# Shawn_sMega.net
KiCad netlist of a schematic drawn in EAGLE
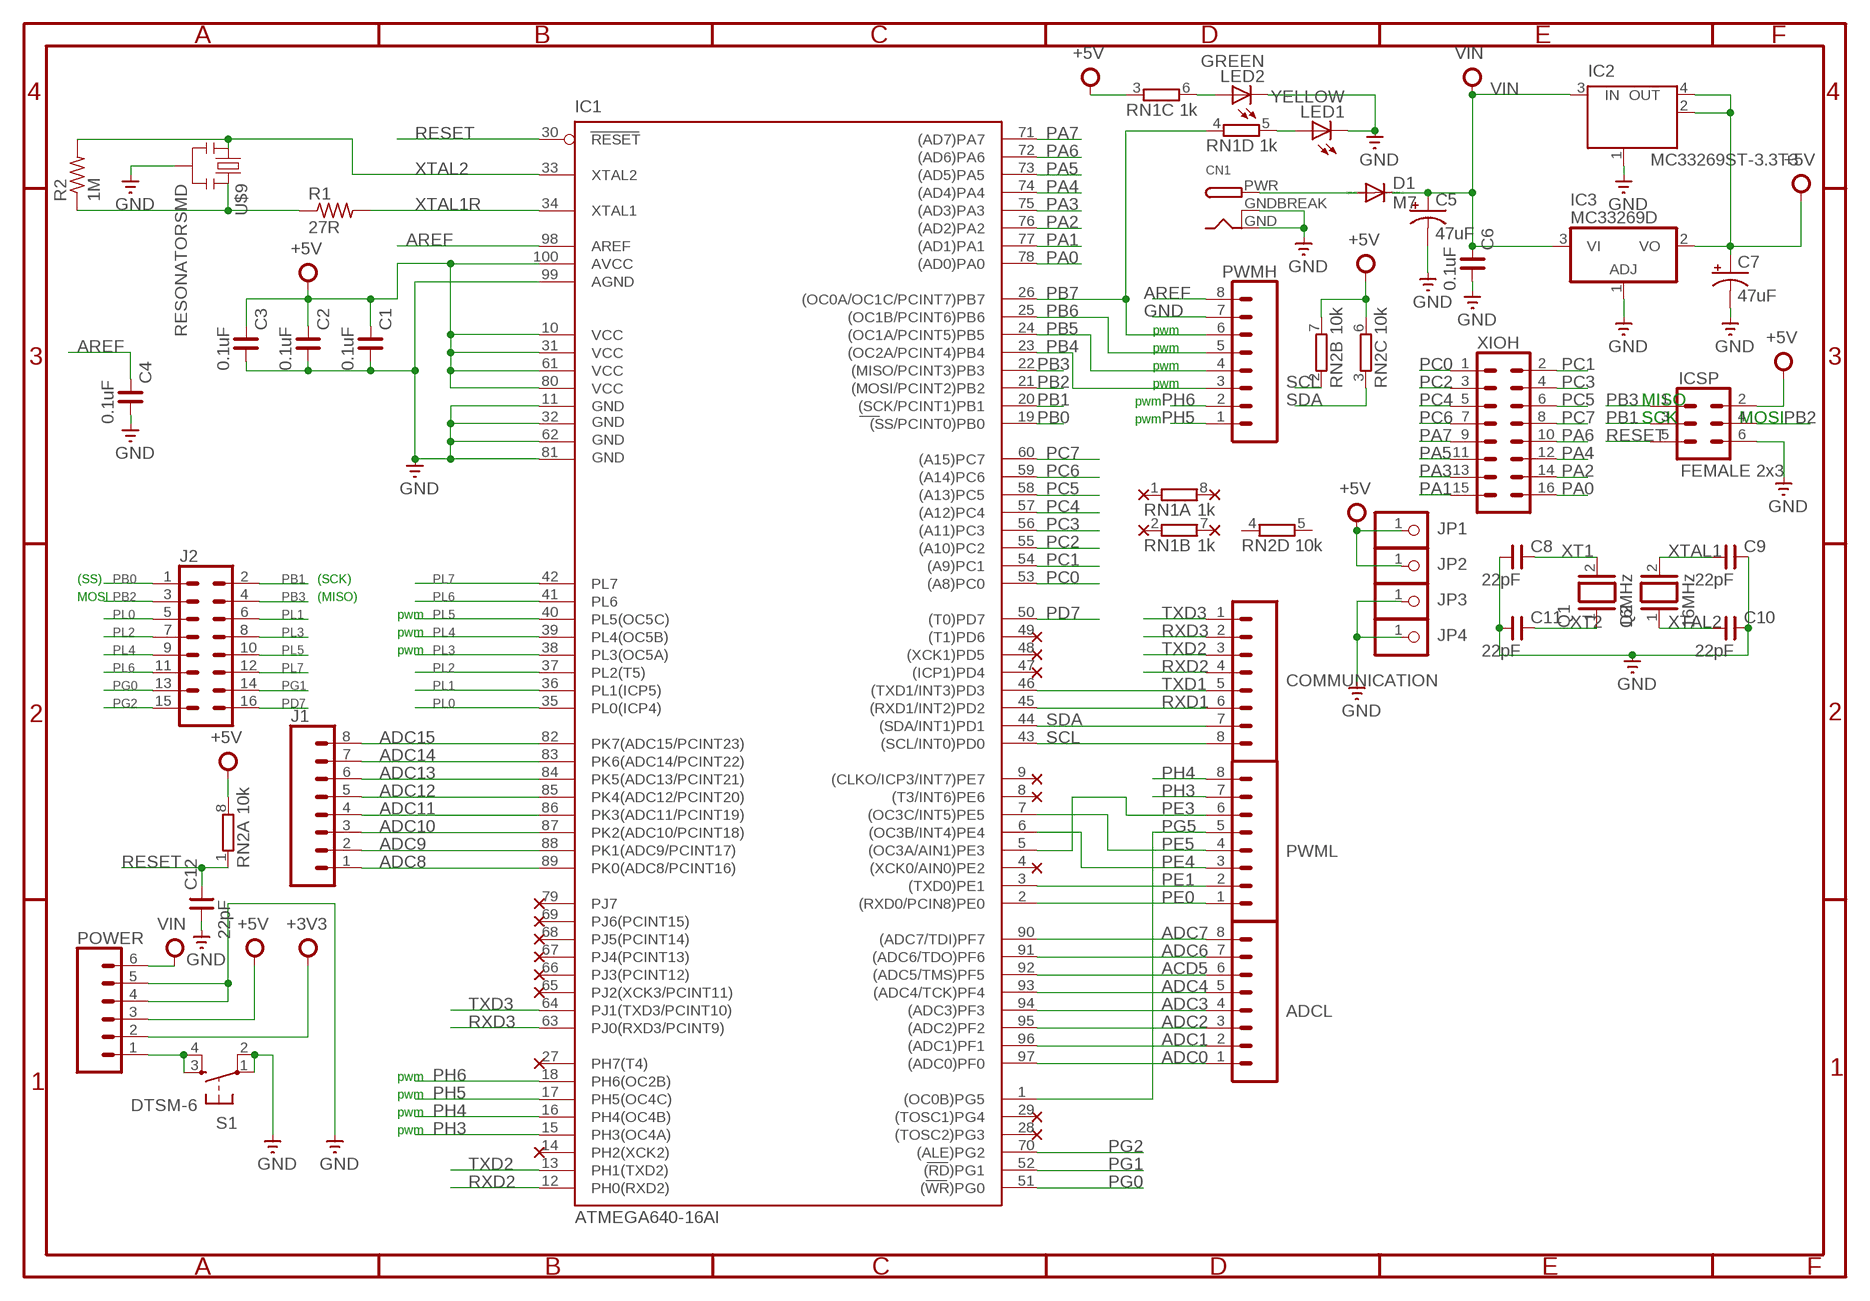
[diagram p0: schematic, sheet 1, part 1 of 2]
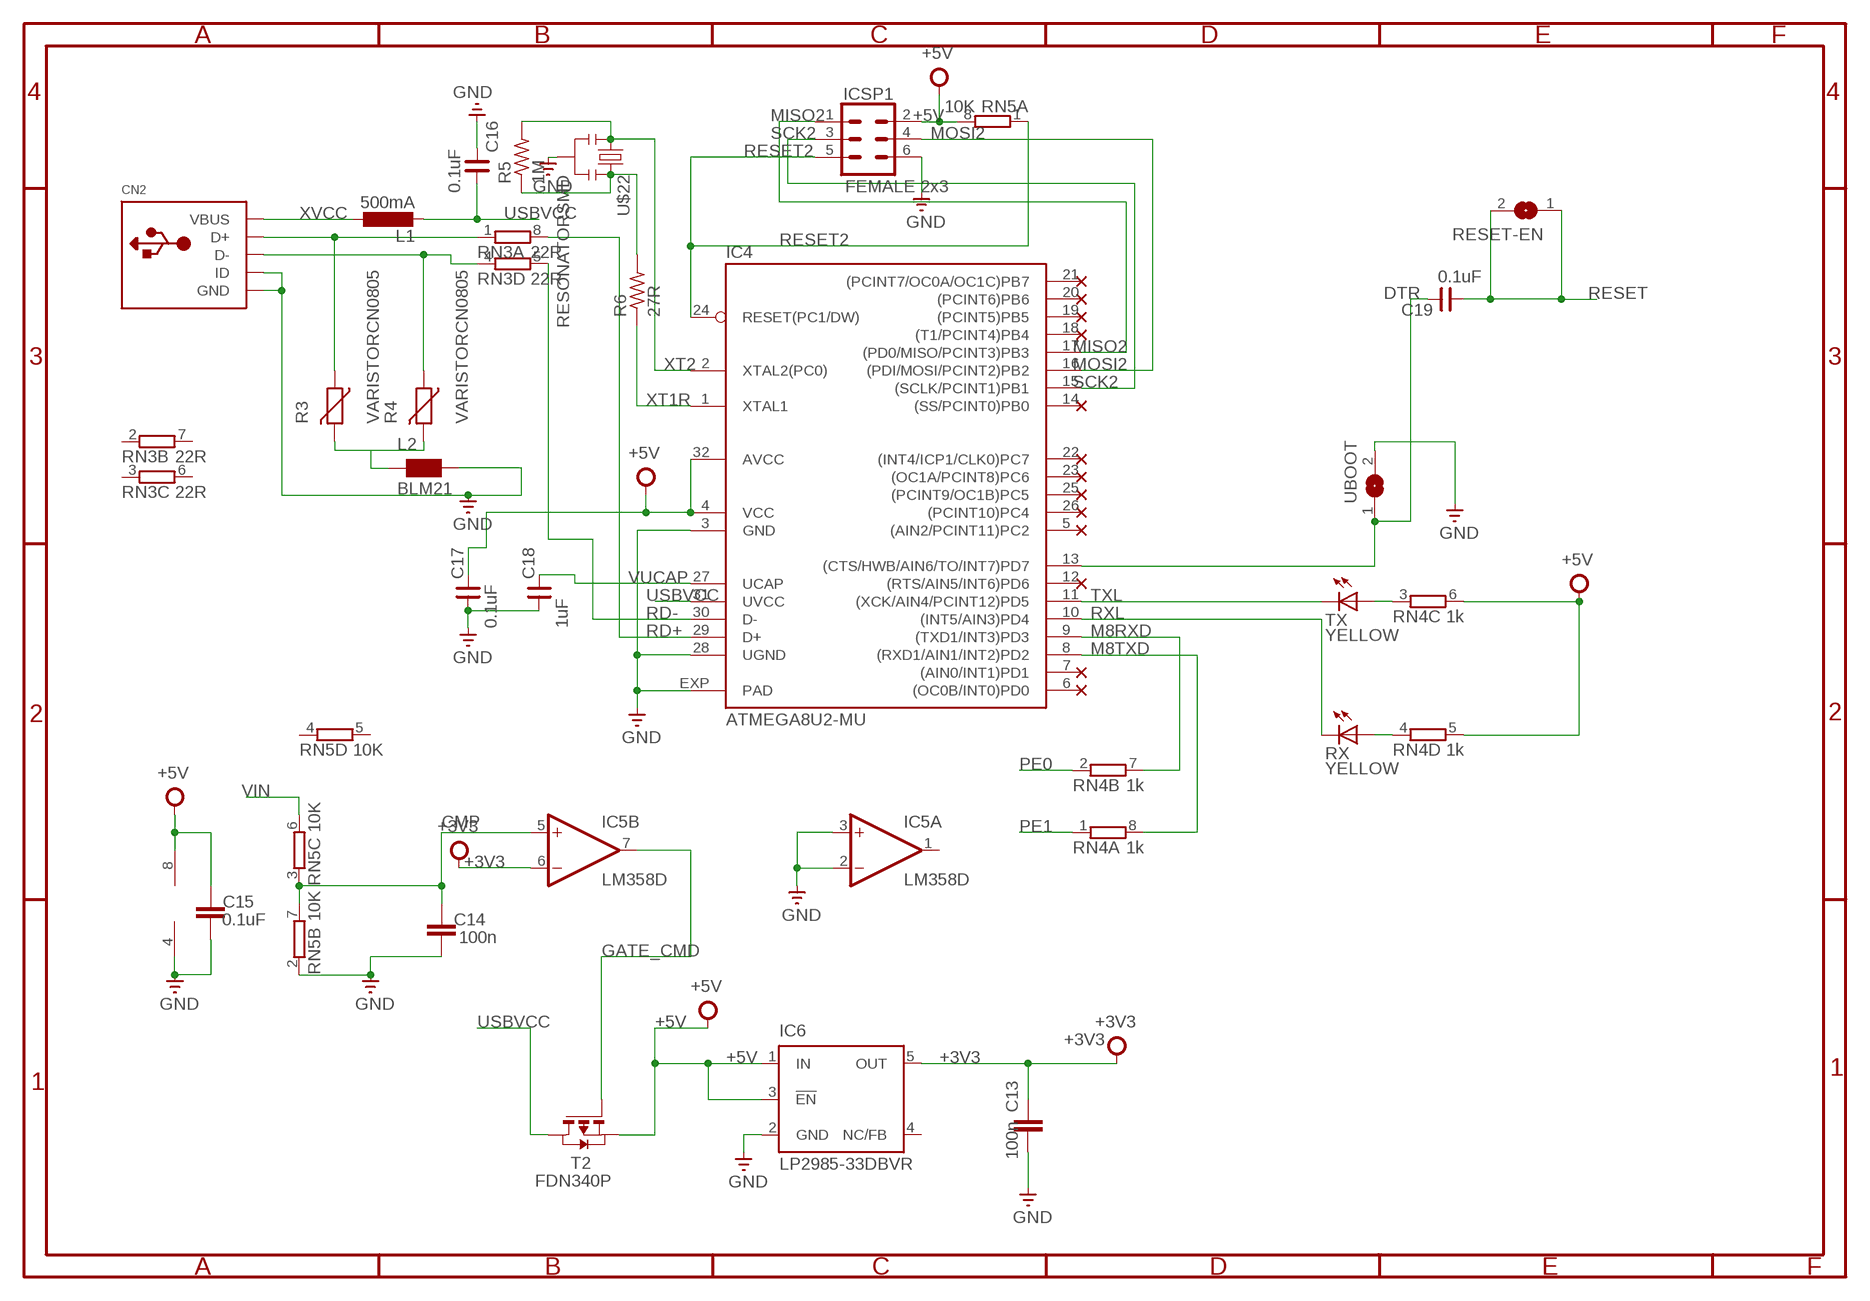
[diagram p1: schematic, sheet 1, part 2 of 2]

(export (version "E")
  (design (tool "Eeschema 10.0.6"))
  (components
    (comp (ref "ADCL")
      (value "CONN_08\"")
      (footprint "eagle-import:1X08")
      (libsource (lib "eagle-import") (part "CONN_08{dblquote}"))
    )
    (comp (ref "C1")
      (value "0.1uF")
      (footprint "eagle-import:C0805")
      (libsource (lib "eagle-import") (part "C_0805"))
    )
    (comp (ref "C2")
      (value "0.1uF")
      (footprint "eagle-import:C0805")
      (libsource (lib "eagle-import") (part "C_0805"))
    )
    (comp (ref "C3")
      (value "0.1uF")
      (footprint "eagle-import:C0805")
      (libsource (lib "eagle-import") (part "C_0805"))
    )
    (comp (ref "C4")
      (value "0.1uF")
      (footprint "eagle-import:C0805")
      (libsource (lib "eagle-import") (part "C_0805"))
    )
    (comp (ref "C5")
      (value "47uF")
      (footprint "eagle-import:PANASONIC_D")
      (libsource (lib "eagle-import") (part "CPOL-USD"))
    )
    (comp (ref "C6")
      (value "0.1uF")
      (footprint "eagle-import:C0805")
      (libsource (lib "eagle-import") (part "C_0805"))
    )
    (comp (ref "C7")
      (value "47uF")
      (footprint "eagle-import:PANASONIC_D")
      (libsource (lib "eagle-import") (part "CPOL-USD"))
    )
    (comp (ref "C8")
      (value "22pF")
      (footprint "eagle-import:0805")
      (libsource (lib "eagle-import") (part "CNP-0805"))
    )
    (comp (ref "C9")
      (value "22pF")
      (footprint "eagle-import:0805")
      (libsource (lib "eagle-import") (part "CNP-0805"))
    )
    (comp (ref "C10")
      (value "22pF")
      (footprint "eagle-import:0805")
      (libsource (lib "eagle-import") (part "CNP-0805"))
    )
    (comp (ref "C11")
      (value "22pF")
      (footprint "eagle-import:0805")
      (libsource (lib "eagle-import") (part "CNP-0805"))
    )
    (comp (ref "C12")
      (value "22pF")
      (footprint "eagle-import:0805")
      (libsource (lib "eagle-import") (part "CNP-0805"))
    )
    (comp (ref "C13")
      (value "100n")
      (footprint "eagle-import:C0603-ROUND")
      (libsource (lib "eagle-import") (part "C-EU0603-RND"))
    )
    (comp (ref "C14")
      (value "100n")
      (footprint "eagle-import:C0603-ROUND")
      (libsource (lib "eagle-import") (part "C-EU0603-RND"))
    )
    (comp (ref "C15")
      (value "0.1uF")
      (footprint "eagle-import:C0603")
      (libsource (lib "eagle-import") (part "rcl_C-EUC0603"))
    )
    (comp (ref "C16")
      (value "0.1uF")
      (footprint "eagle-import:C0805")
      (libsource (lib "eagle-import") (part "C_0805"))
    )
    (comp (ref "C17")
      (value "0.1uF")
      (footprint "eagle-import:0805")
      (libsource (lib "eagle-import") (part "CNP-0805"))
    )
    (comp (ref "C18")
      (value "1uF")
      (footprint "eagle-import:0805")
      (libsource (lib "eagle-import") (part "CNP-0805"))
    )
    (comp (ref "C19")
      (value "0.1uF")
      (footprint "eagle-import:0805")
      (libsource (lib "eagle-import") (part "CNP-0805"))
    )
    (comp (ref "CN1")
      (value "DCBARRELPTH")
      (footprint "eagle-import:DCJACK_2MM_PTH")
      (libsource (lib "eagle-import") (part "DCBARRELPTH"))
    )
    (comp (ref "CN2")
      (value "USBMINIB")
      (footprint "eagle-import:USB-MINIB")
      (libsource (lib "eagle-import") (part "USBMINIB"))
    )
    (comp (ref "COMMUNICATION")
      (value "CONN_08\"")
      (footprint "eagle-import:1X08")
      (libsource (lib "eagle-import") (part "CONN_08{dblquote}"))
    )
    (comp (ref "D1")
      (value "M7")
      (footprint "eagle-import:SMB")
      (libsource (lib "eagle-import") (part "DIODE-SMB"))
    )
    (comp (ref "IC1")
      (value "ATMEGA640-16AI")
      (footprint "eagle-import:TQFP100")
      (libsource (lib "eagle-import") (part "ATMEGAAI640-16"))
    )
    (comp (ref "IC2")
      (value "MC33269ST-3.3T3")
      (footprint "eagle-import:SOT223")
      (libsource (lib "eagle-import") (part "MC33269ST-3.3T3"))
    )
    (comp (ref "IC3")
      (value "MC33269D")
      (footprint "eagle-import:DPACK")
      (libsource (lib "eagle-import") (part "MC33269?D"))
    )
    (comp (ref "IC4")
      (value "ATMEGA8U2-MU")
      (footprint "eagle-import:QFN32")
      (libsource (lib "eagle-import") (part "ATMEGA8U2-MU"))
    )
    (comp (ref "IC5")
      (value "LM358D")
      (footprint "eagle-import:SO08")
      (libsource (lib "eagle-import") (part "LM358D"))
    )
    (comp (ref "IC6")
      (value "LP2985-33DBVR")
      (footprint "eagle-import:SOT23-DBV")
      (libsource (lib "eagle-import") (part "TPS77033"))
    )
    (comp (ref "ICSP")
      (value "FEMALE 2x3")
      (footprint "eagle-import:2X3")
      (libsource (lib "eagle-import") (part "CONN_03X2FEMALE"))
    )
    (comp (ref "ICSP1")
      (value "FEMALE 2x3")
      (footprint "eagle-import:2X3")
      (libsource (lib "eagle-import") (part "CONN_03X2FEMALE"))
    )
    (comp (ref "J1")
      (value "CONN_08\"")
      (footprint "eagle-import:1X08")
      (libsource (lib "eagle-import") (part "CONN_08{dblquote}"))
    )
    (comp (ref "J2")
      (value "CONN_08X2")
      (footprint "eagle-import:2X8")
      (libsource (lib "eagle-import") (part "CONN_08X2"))
    )
    (comp (ref "JP1")
      (value "PINHD-1X1")
      (footprint "eagle-import:1X01")
      (libsource (lib "eagle-import") (part "PINHD-1X1"))
    )
    (comp (ref "JP2")
      (value "PINHD-1X1")
      (footprint "eagle-import:1X01")
      (libsource (lib "eagle-import") (part "PINHD-1X1"))
    )
    (comp (ref "JP3")
      (value "PINHD-1X1")
      (footprint "eagle-import:1X01")
      (libsource (lib "eagle-import") (part "PINHD-1X1"))
    )
    (comp (ref "JP4")
      (value "PINHD-1X1")
      (footprint "eagle-import:1X01")
      (libsource (lib "eagle-import") (part "PINHD-1X1"))
    )
    (comp (ref "L1")
      (value "500mA")
      (footprint "eagle-import:L1812")
      (libsource (lib "eagle-import") (part "L-EUL1812"))
    )
    (comp (ref "L2")
      (value "BLM21")
      (footprint "eagle-import:0805")
      (libsource (lib "eagle-import") (part "WE-CBF_0805"))
    )
    (comp (ref "LED1")
      (value "YELLOW")
      (footprint "eagle-import:CHIPLED_0805")
      (libsource (lib "eagle-import") (part "LEDCHIPLED_0805"))
    )
    (comp (ref "LED2")
      (value "GREEN")
      (footprint "eagle-import:CHIPLED_0805")
      (libsource (lib "eagle-import") (part "LEDCHIPLED_0805"))
    )
    (comp (ref "POWER")
      (value "CONN_06SILK_FEMALE_PTH")
      (footprint "eagle-import:1X06")
      (libsource (lib "eagle-import") (part "CONN_06SILK_FEMALE_PTH"))
    )
    (comp (ref "PWMH")
      (value "CONN_08\"")
      (footprint "eagle-import:1X08")
      (libsource (lib "eagle-import") (part "CONN_08{dblquote}"))
    )
    (comp (ref "PWML")
      (value "CONN_08\"")
      (footprint "eagle-import:1X08")
      (libsource (lib "eagle-import") (part "CONN_08{dblquote}"))
    )
    (comp (ref "Q1")
      (value "16MHz")
      (footprint "eagle-import:QS")
      (libsource (lib "eagle-import") (part "XTAL/S"))
    )
    (comp (ref "Q2")
      (value "16MHz")
      (footprint "eagle-import:QS")
      (libsource (lib "eagle-import") (part "XTAL/S"))
    )
    (comp (ref "R1")
      (value "27R")
      (footprint "eagle-import:R0805")
      (libsource (lib "eagle-import") (part "R-US_R0805"))
    )
    (comp (ref "R2")
      (value "1M")
      (footprint "eagle-import:R0805")
      (libsource (lib "eagle-import") (part "R-US_R0805"))
    )
    (comp (ref "R3")
      (value "VARISTORCN0805")
      (footprint "eagle-import:CT_CN0805")
      (libsource (lib "eagle-import") (part "VARISTORCN0805"))
    )
    (comp (ref "R4")
      (value "VARISTORCN0805")
      (footprint "eagle-import:CT_CN0805")
      (libsource (lib "eagle-import") (part "VARISTORCN0805"))
    )
    (comp (ref "R5")
      (value "1M")
      (footprint "eagle-import:R0805")
      (libsource (lib "eagle-import") (part "R-US_R0805"))
    )
    (comp (ref "R6")
      (value "27R")
      (footprint "eagle-import:R0805")
      (libsource (lib "eagle-import") (part "R-US_R0805"))
    )
    (comp (ref "RESET-EN")
      (value "SJ")
      (footprint "eagle-import:SJ")
      (libsource (lib "eagle-import") (part "SJ"))
    )
    (comp (ref "RN1")
      (value "1k")
      (footprint "eagle-import:CAY16")
      (libsource (lib "eagle-import") (part "resistor-dil_342_4R-NCAY16"))
    )
    (comp (ref "RN2")
      (value "10k")
      (footprint "eagle-import:CAY16")
      (libsource (lib "eagle-import") (part "resistor-dil_342_4R-NCAY16"))
    )
    (comp (ref "RN3")
      (value "22R")
      (footprint "eagle-import:CAT16")
      (libsource (lib "eagle-import") (part "4R-NCAT16"))
    )
    (comp (ref "RN4")
      (value "1k")
      (footprint "eagle-import:CAY16")
      (libsource (lib "eagle-import") (part "resistor-dil_342_4R-NCAY16"))
    )
    (comp (ref "RN5")
      (value "10K")
      (footprint "eagle-import:CAT16")
      (libsource (lib "eagle-import") (part "4R-NCAT16"))
    )
    (comp (ref "RX")
      (value "YELLOW")
      (footprint "eagle-import:CHIPLED_0805")
      (libsource (lib "eagle-import") (part "LEDCHIPLED_0805"))
    )
    (comp (ref "S1")
      (value "DTSM-6")
      (footprint "eagle-import:DTSM-6")
      (libsource (lib "eagle-import") (part "DTSM-6"))
    )
    (comp (ref "T2")
      (value "FDN340P")
      (footprint "eagle-import:SOT-23")
      (libsource (lib "eagle-import") (part "PMOSSOT23"))
    )
    (comp (ref "TX")
      (value "YELLOW")
      (footprint "eagle-import:CHIPLED_0805")
      (libsource (lib "eagle-import") (part "LEDCHIPLED_0805"))
    )
    (comp (ref "U$1") (value "NC") (footprint "eagle-import:NC") (libsource (lib "eagle-import") (part "NC")))
    (comp (ref "U$2") (value "NC") (footprint "eagle-import:NC") (libsource (lib "eagle-import") (part "NC")))
    (comp (ref "U$3") (value "NC") (footprint "eagle-import:NC") (libsource (lib "eagle-import") (part "NC")))
    (comp (ref "U$4") (value "NC") (footprint "eagle-import:NC") (libsource (lib "eagle-import") (part "NC")))
    (comp (ref "U$5") (value "NC") (footprint "eagle-import:NC") (libsource (lib "eagle-import") (part "NC")))
    (comp (ref "U$6") (value "NC") (footprint "eagle-import:NC") (libsource (lib "eagle-import") (part "NC")))
    (comp (ref "U$7") (value "NC") (footprint "eagle-import:NC") (libsource (lib "eagle-import") (part "NC")))
    (comp (ref "U$8") (value "NC") (footprint "eagle-import:NC") (libsource (lib "eagle-import") (part "NC")))
    (comp (ref "U$9")
      (value "RESONATORSMD")
      (footprint "eagle-import:RESONATOR-SMD")
      (libsource (lib "eagle-import") (part "RESONATORSMD"))
    )
    (comp (ref "U$10")
      (value "NC")
      (footprint "eagle-import:NC")
      (libsource (lib "eagle-import") (part "NC"))
    )
    (comp (ref "U$11")
      (value "NC")
      (footprint "eagle-import:NC")
      (libsource (lib "eagle-import") (part "NC"))
    )
    (comp (ref "U$12")
      (value "NC")
      (footprint "eagle-import:NC")
      (libsource (lib "eagle-import") (part "NC"))
    )
    (comp (ref "U$13")
      (value "NC")
      (footprint "eagle-import:NC")
      (libsource (lib "eagle-import") (part "NC"))
    )
    (comp (ref "U$14")
      (value "NC")
      (footprint "eagle-import:NC")
      (libsource (lib "eagle-import") (part "NC"))
    )
    (comp (ref "U$15")
      (value "NC")
      (footprint "eagle-import:NC")
      (libsource (lib "eagle-import") (part "NC"))
    )
    (comp (ref "U$16")
      (value "NC")
      (footprint "eagle-import:NC")
      (libsource (lib "eagle-import") (part "NC"))
    )
    (comp (ref "U$17")
      (value "NC")
      (footprint "eagle-import:NC")
      (libsource (lib "eagle-import") (part "NC"))
    )
    (comp (ref "U$18")
      (value "NC")
      (footprint "eagle-import:NC")
      (libsource (lib "eagle-import") (part "NC"))
    )
    (comp (ref "U$19")
      (value "NC")
      (footprint "eagle-import:NC")
      (libsource (lib "eagle-import") (part "NC"))
    )
    (comp (ref "U$20")
      (value "NC")
      (footprint "eagle-import:NC")
      (libsource (lib "eagle-import") (part "NC"))
    )
    (comp (ref "U$21")
      (value "NC")
      (footprint "eagle-import:NC")
      (libsource (lib "eagle-import") (part "NC"))
    )
    (comp (ref "U$22")
      (value "RESONATORSMD")
      (footprint "eagle-import:RESONATOR-SMD")
      (libsource (lib "eagle-import") (part "RESONATORSMD"))
    )
    (comp (ref "U$23")
      (value "NC")
      (footprint "eagle-import:NC")
      (libsource (lib "eagle-import") (part "NC"))
    )
    (comp (ref "U$24")
      (value "NC")
      (footprint "eagle-import:NC")
      (libsource (lib "eagle-import") (part "NC"))
    )
    (comp (ref "U$25")
      (value "NC")
      (footprint "eagle-import:NC")
      (libsource (lib "eagle-import") (part "NC"))
    )
    (comp (ref "U$26")
      (value "NC")
      (footprint "eagle-import:NC")
      (libsource (lib "eagle-import") (part "NC"))
    )
    (comp (ref "U$27")
      (value "NC")
      (footprint "eagle-import:NC")
      (libsource (lib "eagle-import") (part "NC"))
    )
    (comp (ref "U$28")
      (value "NC")
      (footprint "eagle-import:NC")
      (libsource (lib "eagle-import") (part "NC"))
    )
    (comp (ref "U$29")
      (value "NC")
      (footprint "eagle-import:NC")
      (libsource (lib "eagle-import") (part "NC"))
    )
    (comp (ref "U$30")
      (value "NC")
      (footprint "eagle-import:NC")
      (libsource (lib "eagle-import") (part "NC"))
    )
    (comp (ref "U$31")
      (value "NC")
      (footprint "eagle-import:NC")
      (libsource (lib "eagle-import") (part "NC"))
    )
    (comp (ref "U$32")
      (value "NC")
      (footprint "eagle-import:NC")
      (libsource (lib "eagle-import") (part "NC"))
    )
    (comp (ref "U$33")
      (value "NC")
      (footprint "eagle-import:NC")
      (libsource (lib "eagle-import") (part "NC"))
    )
    (comp (ref "U$34")
      (value "NC")
      (footprint "eagle-import:NC")
      (libsource (lib "eagle-import") (part "NC"))
    )
    (comp (ref "U$35")
      (value "NC")
      (footprint "eagle-import:NC")
      (libsource (lib "eagle-import") (part "NC"))
    )
    (comp (ref "UBOOT")
      (value "SJ")
      (footprint "eagle-import:SJ")
      (libsource (lib "eagle-import") (part "SJ"))
    )
    (comp (ref "XIOH")
      (value "CONN_08X2")
      (footprint "eagle-import:2X8")
      (libsource (lib "eagle-import") (part "CONN_08X2"))
    )
  )
  (nets
    (net (code "1") (name "+3V3") (class "Default")
      (node (ref "C13") (pin "2") (pinfunction "2_2") (pintype "passive"))
      (node (ref "IC5") (pin "6") (pinfunction "-IN_6") (pintype "input"))
      (node (ref "IC6") (pin "5") (pinfunction "OUT_5") (pintype "passive"))
      (node (ref "POWER") (pin "2") (pinfunction "2_2") (pintype "passive"))
    )
    (net (code "2") (name "+5V") (class "Default")
      (node (ref "C1") (pin "2") (pinfunction "2_2") (pintype "passive"))
      (node (ref "C15") (pin "2") (pinfunction "2_2") (pintype "passive"))
      (node (ref "C17") (pin "2") (pinfunction "2_2") (pintype "passive"))
      (node (ref "C2") (pin "2") (pinfunction "2_2") (pintype "passive"))
      (node (ref "C3") (pin "2") (pinfunction "2_2") (pintype "passive"))
      (node (ref "C7") (pin "+") (pinfunction "+_+") (pintype "passive"))
      (node (ref "IC1") (pin "10") (pinfunction "VCC_10") (pintype "power_in"))
      (node (ref "IC1") (pin "100") (pinfunction "AVCC_100") (pintype "power_in"))
      (node (ref "IC1") (pin "31") (pinfunction "VCC1_31") (pintype "power_in"))
      (node (ref "IC1") (pin "61") (pinfunction "VCC2_61") (pintype "power_in"))
      (node (ref "IC1") (pin "80") (pinfunction "VCC3_80") (pintype "power_in"))
      (node (ref "IC2") (pin "2") (pinfunction "OUT_2") (pintype "passive"))
      (node (ref "IC2") (pin "4") (pinfunction "OUT_4") (pintype "passive"))
      (node (ref "IC3") (pin "2") (pinfunction "VO_2") (pintype "passive"))
      (node (ref "IC4") (pin "32") (pinfunction "AVCC_32") (pintype "power_in"))
      (node (ref "IC4") (pin "4") (pinfunction "VCC_4") (pintype "power_in"))
      (node (ref "IC5") (pin "8") (pinfunction "V+_8") (pintype "power_in"))
      (node (ref "IC6") (pin "1") (pinfunction "IN_1") (pintype "input"))
      (node (ref "IC6") (pin "3") (pinfunction "~{EN}_3") (pintype "input"))
      (node (ref "ICSP") (pin "2") (pinfunction "2_2") (pintype "bidirectional"))
      (node (ref "ICSP1") (pin "2") (pinfunction "2_2") (pintype "bidirectional"))
      (node (ref "JP1") (pin "1") (pinfunction "1_1") (pintype "passive"))
      (node (ref "JP2") (pin "1") (pinfunction "1_1") (pintype "passive"))
      (node (ref "POWER") (pin "3") (pinfunction "3_3") (pintype "passive"))
      (node (ref "RN1") (pin "3") (pinfunction "1_3") (pintype "passive"))
      (node (ref "RN2") (pin "6") (pinfunction "2_6") (pintype "passive"))
      (node (ref "RN2") (pin "7") (pinfunction "2_7") (pintype "passive"))
      (node (ref "RN2") (pin "8") (pinfunction "2_8") (pintype "passive"))
      (node (ref "RN4") (pin "5") (pinfunction "2_5") (pintype "passive"))
      (node (ref "RN4") (pin "6") (pinfunction "2_6") (pintype "passive"))
      (node (ref "RN5") (pin "8") (pinfunction "2_8") (pintype "passive"))
      (node (ref "T2") (pin "2") (pinfunction "S_2") (pintype "passive"))
    )
    (net (code "3") (name "/ACD5") (class "Default")
      (node (ref "ADCL") (pin "6") (pinfunction "6_6") (pintype "passive"))
      (node (ref "IC1") (pin "92") (pinfunction "(ADC5/TMS)PF5_92") (pintype "bidirectional"))
    )
    (net (code "4") (name "/ADC0") (class "Default")
      (node (ref "ADCL") (pin "1") (pinfunction "1_1") (pintype "passive"))
      (node (ref "IC1") (pin "97") (pinfunction "(ADC0)PF0_97") (pintype "bidirectional"))
    )
    (net (code "5") (name "/ADC1") (class "Default")
      (node (ref "ADCL") (pin "2") (pinfunction "2_2") (pintype "passive"))
      (node (ref "IC1") (pin "96") (pinfunction "(ADC1)PF1_96") (pintype "bidirectional"))
    )
    (net (code "6") (name "/ADC2") (class "Default")
      (node (ref "ADCL") (pin "3") (pinfunction "3_3") (pintype "passive"))
      (node (ref "IC1") (pin "95") (pinfunction "(ADC2)PF2_95") (pintype "bidirectional"))
    )
    (net (code "7") (name "/ADC3") (class "Default")
      (node (ref "ADCL") (pin "4") (pinfunction "4_4") (pintype "passive"))
      (node (ref "IC1") (pin "94") (pinfunction "(ADC3)PF3_94") (pintype "bidirectional"))
    )
    (net (code "8") (name "/ADC4") (class "Default")
      (node (ref "ADCL") (pin "5") (pinfunction "5_5") (pintype "passive"))
      (node (ref "IC1") (pin "93") (pinfunction "(ADC4/TCK)PF4_93") (pintype "bidirectional"))
    )
    (net (code "9") (name "/ADC6") (class "Default")
      (node (ref "ADCL") (pin "7") (pinfunction "7_7") (pintype "passive"))
      (node (ref "IC1") (pin "91") (pinfunction "(ADC6/TDO)PF6_91") (pintype "bidirectional"))
    )
    (net (code "10") (name "/ADC7") (class "Default")
      (node (ref "ADCL") (pin "8") (pinfunction "8_8") (pintype "passive"))
      (node (ref "IC1") (pin "90") (pinfunction "(ADC7/TDI)PF7_90") (pintype "bidirectional"))
    )
    (net (code "11") (name "/ADC8") (class "Default")
      (node (ref "IC1") (pin "89") (pinfunction "PK0(ADC8/PCINT16)_89") (pintype "bidirectional"))
      (node (ref "J1") (pin "1") (pinfunction "1_1") (pintype "passive"))
    )
    (net (code "12") (name "/ADC9") (class "Default")
      (node (ref "IC1") (pin "88") (pinfunction "PK1(ADC9/PCINT17)_88") (pintype "bidirectional"))
      (node (ref "J1") (pin "2") (pinfunction "2_2") (pintype "passive"))
    )
    (net (code "13") (name "/ADC10") (class "Default")
      (node (ref "IC1") (pin "87") (pinfunction "PK2(ADC10/PCINT18)_87") (pintype "bidirectional"))
      (node (ref "J1") (pin "3") (pinfunction "3_3") (pintype "passive"))
    )
    (net (code "14") (name "/ADC11") (class "Default")
      (node (ref "IC1") (pin "86") (pinfunction "PK3(ADC11/PCINT19)_86") (pintype "bidirectional"))
      (node (ref "J1") (pin "4") (pinfunction "4_4") (pintype "passive"))
    )
    (net (code "15") (name "/ADC12") (class "Default")
      (node (ref "IC1") (pin "85") (pinfunction "PK4(ADC12/PCINT20)_85") (pintype "bidirectional"))
      (node (ref "J1") (pin "5") (pinfunction "5_5") (pintype "passive"))
    )
    (net (code "16") (name "/ADC13") (class "Default")
      (node (ref "IC1") (pin "84") (pinfunction "PK5(ADC13/PCINT21)_84") (pintype "bidirectional"))
      (node (ref "J1") (pin "6") (pinfunction "6_6") (pintype "passive"))
    )
    (net (code "17") (name "/ADC14") (class "Default")
      (node (ref "IC1") (pin "83") (pinfunction "PK6(ADC14/PCINT22)_83") (pintype "bidirectional"))
      (node (ref "J1") (pin "7") (pinfunction "7_7") (pintype "passive"))
    )
    (net (code "18") (name "/ADC15") (class "Default")
      (node (ref "IC1") (pin "82") (pinfunction "PK7(ADC15/PCINT23)_82") (pintype "bidirectional"))
      (node (ref "J1") (pin "8") (pinfunction "8_8") (pintype "passive"))
    )
    (net (code "19") (name "/AREF") (class "Default")
      (node (ref "C4") (pin "2") (pinfunction "2_2") (pintype "passive"))
      (node (ref "IC1") (pin "98") (pinfunction "AREF_98") (pintype "bidirectional"))
      (node (ref "PWMH") (pin "8") (pinfunction "8_8") (pintype "passive"))
    )
    (net (code "20") (name "/CMP") (class "Default")
      (node (ref "C14") (pin "2") (pinfunction "2_2") (pintype "passive"))
      (node (ref "IC5") (pin "5") (pinfunction "+IN_5") (pintype "input"))
      (node (ref "RN5") (pin "3") (pinfunction "1_3") (pintype "passive"))
      (node (ref "RN5") (pin "7") (pinfunction "2_7") (pintype "passive"))
    )
    (net (code "21") (name "/DTR") (class "Default")
      (node (ref "C19") (pin "2") (pinfunction "2_2") (pintype "passive"))
      (node (ref "IC4") (pin "13") (pinfunction "(CTS/HWB/AIN6/TO/INT7)PD7_13") (pintype "bidirectional"))
      (node (ref "UBOOT") (pin "1") (pinfunction "1_1") (pintype "passive"))
    )
    (net (code "22") (name "/GATE_CMD") (class "Default")
      (node (ref "IC5") (pin "7") (pinfunction "OUT_7") (pintype "output"))
      (node (ref "T2") (pin "3") (pinfunction "G_3") (pintype "passive"))
    )
    (net (code "23") (name "/M8RXD") (class "Default")
      (node (ref "IC4") (pin "9") (pinfunction "(TXD1/INT3)PD3_9") (pintype "bidirectional"))
      (node (ref "RN4") (pin "7") (pinfunction "2_7") (pintype "passive"))
    )
    (net (code "24") (name "/M8TXD") (class "Default")
      (node (ref "IC4") (pin "8") (pinfunction "(RXD1/AIN1/INT2)PD2_8") (pintype "bidirectional"))
      (node (ref "RN4") (pin "8") (pinfunction "2_8") (pintype "passive"))
    )
    (net (code "25") (name "/MISO2") (class "Default")
      (node (ref "IC4") (pin "17") (pinfunction "(PD0/MISO/PCINT3)PB3_17") (pintype "bidirectional"))
      (node (ref "ICSP1") (pin "1") (pinfunction "1_1") (pintype "bidirectional"))
    )
    (net (code "26") (name "/MOSI2") (class "Default")
      (node (ref "IC4") (pin "16") (pinfunction "(PDI/MOSI/PCINT2)PB2_16") (pintype "bidirectional"))
      (node (ref "ICSP1") (pin "4") (pinfunction "4_4") (pintype "bidirectional"))
    )
    (net (code "27") (name "/PA0") (class "Default")
      (node (ref "IC1") (pin "78") (pinfunction "(AD0)PA0_78") (pintype "bidirectional"))
      (node (ref "XIOH") (pin "16") (pinfunction "16_16") (pintype "passive"))
    )
    (net (code "28") (name "/PA1") (class "Default")
      (node (ref "IC1") (pin "77") (pinfunction "(AD1)PA1_77") (pintype "bidirectional"))
      (node (ref "XIOH") (pin "15") (pinfunction "15_15") (pintype "passive"))
    )
    (net (code "29") (name "/PA2") (class "Default")
      (node (ref "IC1") (pin "76") (pinfunction "(AD2)PA2_76") (pintype "bidirectional"))
      (node (ref "XIOH") (pin "14") (pinfunction "14_14") (pintype "passive"))
    )
    (net (code "30") (name "/PA3") (class "Default")
      (node (ref "IC1") (pin "75") (pinfunction "(AD3)PA3_75") (pintype "bidirectional"))
      (node (ref "XIOH") (pin "13") (pinfunction "13_13") (pintype "passive"))
    )
    (net (code "31") (name "/PA4") (class "Default")
      (node (ref "IC1") (pin "74") (pinfunction "(AD4)PA4_74") (pintype "bidirectional"))
      (node (ref "XIOH") (pin "12") (pinfunction "12_12") (pintype "passive"))
    )
    (net (code "32") (name "/PA5") (class "Default")
      (node (ref "IC1") (pin "73") (pinfunction "(AD5)PA5_73") (pintype "bidirectional"))
      (node (ref "XIOH") (pin "11") (pinfunction "11_11") (pintype "passive"))
    )
    (net (code "33") (name "/PA6") (class "Default")
      (node (ref "IC1") (pin "72") (pinfunction "(AD6)PA6_72") (pintype "bidirectional"))
      (node (ref "XIOH") (pin "10") (pinfunction "10_10") (pintype "passive"))
    )
    (net (code "34") (name "/PA7") (class "Default")
      (node (ref "IC1") (pin "71") (pinfunction "(AD7)PA7_71") (pintype "bidirectional"))
      (node (ref "XIOH") (pin "9") (pinfunction "9_9") (pintype "passive"))
    )
    (net (code "35") (name "/PB0") (class "Default")
      (node (ref "IC1") (pin "19") (pinfunction "(SS/PCINT0)PB0_19") (pintype "bidirectional"))
      (node (ref "J2") (pin "1") (pinfunction "1_1") (pintype "passive"))
    )
    (net (code "36") (name "/PB1") (class "Default")
      (node (ref "IC1") (pin "20") (pinfunction "(SCK/PCINT1)PB1_20") (pintype "bidirectional"))
      (node (ref "ICSP") (pin "3") (pinfunction "3_3") (pintype "bidirectional"))
      (node (ref "J2") (pin "2") (pinfunction "2_2") (pintype "passive"))
    )
    (net (code "37") (name "/PB2") (class "Default")
      (node (ref "IC1") (pin "21") (pinfunction "(MOSI/PCINT2)PB2_21") (pintype "bidirectional"))
      (node (ref "ICSP") (pin "4") (pinfunction "4_4") (pintype "bidirectional"))
      (node (ref "J2") (pin "3") (pinfunction "3_3") (pintype "passive"))
    )
    (net (code "38") (name "/PB3") (class "Default")
      (node (ref "IC1") (pin "22") (pinfunction "(MISO/PCINT3)PB3_22") (pintype "bidirectional"))
      (node (ref "ICSP") (pin "1") (pinfunction "1_1") (pintype "bidirectional"))
      (node (ref "J2") (pin "4") (pinfunction "4_4") (pintype "passive"))
    )
    (net (code "39") (name "/PB4") (class "Default")
      (node (ref "IC1") (pin "23") (pinfunction "(OC2A/PCINT4)PB4_23") (pintype "bidirectional"))
      (node (ref "PWMH") (pin "3") (pinfunction "3_3") (pintype "passive"))
    )
    (net (code "40") (name "/PB5") (class "Default")
      (node (ref "IC1") (pin "24") (pinfunction "(OC1A/PCINT5)PB5_24") (pintype "bidirectional"))
      (node (ref "PWMH") (pin "4") (pinfunction "4_4") (pintype "passive"))
    )
    (net (code "41") (name "/PB6") (class "Default")
      (node (ref "IC1") (pin "25") (pinfunction "(OC1B/PCINT6)PB6_25") (pintype "bidirectional"))
      (node (ref "PWMH") (pin "5") (pinfunction "5_5") (pintype "passive"))
    )
    (net (code "42") (name "/PB7") (class "Default")
      (node (ref "IC1") (pin "26") (pinfunction "(OC0A/OC1C/PCINT7)PB7_26") (pintype "bidirectional"))
      (node (ref "PWMH") (pin "6") (pinfunction "6_6") (pintype "passive"))
      (node (ref "RN1") (pin "4") (pinfunction "1_4") (pintype "passive"))
    )
    (net (code "43") (name "/PC0") (class "Default")
      (node (ref "IC1") (pin "53") (pinfunction "(A8)PC0_53") (pintype "bidirectional"))
      (node (ref "XIOH") (pin "1") (pinfunction "1_1") (pintype "passive"))
    )
    (net (code "44") (name "/PC1") (class "Default")
      (node (ref "IC1") (pin "54") (pinfunction "(A9)PC1_54") (pintype "bidirectional"))
      (node (ref "XIOH") (pin "2") (pinfunction "2_2") (pintype "passive"))
    )
    (net (code "45") (name "/PC2") (class "Default")
      (node (ref "IC1") (pin "55") (pinfunction "(A10)PC2_55") (pintype "bidirectional"))
      (node (ref "XIOH") (pin "3") (pinfunction "3_3") (pintype "passive"))
    )
    (net (code "46") (name "/PC3") (class "Default")
      (node (ref "IC1") (pin "56") (pinfunction "(A11)PC3_56") (pintype "bidirectional"))
      (node (ref "XIOH") (pin "4") (pinfunction "4_4") (pintype "passive"))
    )
    (net (code "47") (name "/PC4") (class "Default")
      (node (ref "IC1") (pin "57") (pinfunction "(A12)PC4_57") (pintype "bidirectional"))
      (node (ref "XIOH") (pin "5") (pinfunction "5_5") (pintype "passive"))
    )
    (net (code "48") (name "/PC5") (class "Default")
      (node (ref "IC1") (pin "58") (pinfunction "(A13)PC5_58") (pintype "bidirectional"))
      (node (ref "XIOH") (pin "6") (pinfunction "6_6") (pintype "passive"))
    )
    (net (code "49") (name "/PC6") (class "Default")
      (node (ref "IC1") (pin "59") (pinfunction "(A14)PC6_59") (pintype "bidirectional"))
      (node (ref "XIOH") (pin "7") (pinfunction "7_7") (pintype "passive"))
    )
    (net (code "50") (name "/PC7") (class "Default")
      (node (ref "IC1") (pin "60") (pinfunction "(A15)PC7_60") (pintype "bidirectional"))
      (node (ref "XIOH") (pin "8") (pinfunction "8_8") (pintype "passive"))
    )
    (net (code "51") (name "/PD7") (class "Default")
      (node (ref "IC1") (pin "50") (pinfunction "(T0)PD7_50") (pintype "bidirectional"))
      (node (ref "J2") (pin "16") (pinfunction "16_16") (pintype "passive"))
    )
    (net (code "52") (name "/PE0") (class "Default")
      (node (ref "IC1") (pin "2") (pinfunction "(RXD0/PCIN8)PE0_2") (pintype "bidirectional"))
      (node (ref "PWML") (pin "1") (pinfunction "1_1") (pintype "passive"))
      (node (ref "RN4") (pin "2") (pinfunction "1_2") (pintype "passive"))
    )
    (net (code "53") (name "/PE1") (class "Default")
      (node (ref "IC1") (pin "3") (pinfunction "(TXD0)PE1_3") (pintype "bidirectional"))
      (node (ref "PWML") (pin "2") (pinfunction "2_2") (pintype "passive"))
      (node (ref "RN4") (pin "1") (pinfunction "1_1") (pintype "passive"))
    )
    (net (code "54") (name "/PE3") (class "Default")
      (node (ref "IC1") (pin "5") (pinfunction "(OC3A/AIN1)PE3_5") (pintype "bidirectional"))
      (node (ref "PWML") (pin "6") (pinfunction "6_6") (pintype "passive"))
    )
    (net (code "55") (name "/PE4") (class "Default")
      (node (ref "IC1") (pin "6") (pinfunction "(OC3B/INT4)PE4_6") (pintype "bidirectional"))
      (node (ref "PWML") (pin "3") (pinfunction "3_3") (pintype "passive"))
    )
    (net (code "56") (name "/PE5") (class "Default")
      (node (ref "IC1") (pin "7") (pinfunction "(OC3C/INT5)PE5_7") (pintype "bidirectional"))
      (node (ref "PWML") (pin "4") (pinfunction "4_4") (pintype "passive"))
    )
    (net (code "57") (name "/PG0") (class "Default")
      (node (ref "IC1") (pin "51") (pinfunction "(WR)PG0_51") (pintype "bidirectional"))
      (node (ref "J2") (pin "13") (pinfunction "13_13") (pintype "passive"))
    )
    (net (code "58") (name "/PG1") (class "Default")
      (node (ref "IC1") (pin "52") (pinfunction "(RD)PG1_52") (pintype "bidirectional"))
      (node (ref "J2") (pin "14") (pinfunction "14_14") (pintype "passive"))
    )
    (net (code "59") (name "/PG2") (class "Default")
      (node (ref "IC1") (pin "70") (pinfunction "(ALE)PG2_70") (pintype "bidirectional"))
      (node (ref "J2") (pin "15") (pinfunction "15_15") (pintype "passive"))
    )
    (net (code "60") (name "/PG5") (class "Default")
      (node (ref "IC1") (pin "1") (pinfunction "(OC0B)PG5_1") (pintype "bidirectional"))
      (node (ref "PWML") (pin "5") (pinfunction "5_5") (pintype "passive"))
    )
    (net (code "61") (name "/PH3") (class "Default")
      (node (ref "IC1") (pin "15") (pinfunction "PH3(OC4A)_15") (pintype "bidirectional"))
      (node (ref "PWML") (pin "7") (pinfunction "7_7") (pintype "passive"))
    )
    (net (code "62") (name "/PH4") (class "Default")
      (node (ref "IC1") (pin "16") (pinfunction "PH4(OC4B)_16") (pintype "bidirectional"))
      (node (ref "PWML") (pin "8") (pinfunction "8_8") (pintype "passive"))
    )
    (net (code "63") (name "/PH5") (class "Default")
      (node (ref "IC1") (pin "17") (pinfunction "PH5(OC4C)_17") (pintype "bidirectional"))
      (node (ref "PWMH") (pin "1") (pinfunction "1_1") (pintype "passive"))
    )
    (net (code "64") (name "/PH6") (class "Default")
      (node (ref "IC1") (pin "18") (pinfunction "PH6(OC2B)_18") (pintype "bidirectional"))
      (node (ref "PWMH") (pin "2") (pinfunction "2_2") (pintype "passive"))
    )
    (net (code "65") (name "/PL0") (class "Default")
      (node (ref "IC1") (pin "35") (pinfunction "PL0(ICP4)_35") (pintype "bidirectional"))
      (node (ref "J2") (pin "5") (pinfunction "5_5") (pintype "passive"))
    )
    (net (code "66") (name "/PL1") (class "Default")
      (node (ref "IC1") (pin "36") (pinfunction "PL1(ICP5)_36") (pintype "bidirectional"))
      (node (ref "J2") (pin "6") (pinfunction "6_6") (pintype "passive"))
    )
    (net (code "67") (name "/PL2") (class "Default")
      (node (ref "IC1") (pin "37") (pinfunction "PL2(T5)_37") (pintype "bidirectional"))
      (node (ref "J2") (pin "7") (pinfunction "7_7") (pintype "passive"))
    )
    (net (code "68") (name "/PL3") (class "Default")
      (node (ref "IC1") (pin "38") (pinfunction "PL3(OC5A)_38") (pintype "bidirectional"))
      (node (ref "J2") (pin "8") (pinfunction "8_8") (pintype "passive"))
    )
    (net (code "69") (name "/PL4") (class "Default")
      (node (ref "IC1") (pin "39") (pinfunction "PL4(OC5B)_39") (pintype "bidirectional"))
      (node (ref "J2") (pin "9") (pinfunction "9_9") (pintype "passive"))
    )
    (net (code "70") (name "/PL5") (class "Default")
      (node (ref "IC1") (pin "40") (pinfunction "PL5(OC5C)_40") (pintype "bidirectional"))
      (node (ref "J2") (pin "10") (pinfunction "10_10") (pintype "passive"))
    )
    (net (code "71") (name "/PL6") (class "Default")
      (node (ref "IC1") (pin "41") (pinfunction "PL6_41") (pintype "bidirectional"))
      (node (ref "J2") (pin "11") (pinfunction "11_11") (pintype "passive"))
    )
    (net (code "72") (name "/PL7") (class "Default")
      (node (ref "IC1") (pin "42") (pinfunction "PL7_42") (pintype "bidirectional"))
      (node (ref "J2") (pin "12") (pinfunction "12_12") (pintype "passive"))
    )
    (net (code "73") (name "/RD+") (class "Default")
      (node (ref "IC4") (pin "29") (pinfunction "D+_29") (pintype "bidirectional"))
      (node (ref "RN3") (pin "8") (pinfunction "2_8") (pintype "passive"))
    )
    (net (code "74") (name "/RD-") (class "Default")
      (node (ref "IC4") (pin "30") (pinfunction "D-_30") (pintype "bidirectional"))
      (node (ref "RN3") (pin "5") (pinfunction "2_5") (pintype "passive"))
    )
    (net (code "75") (name "/RESET") (class "Default")
      (node (ref "C12") (pin "2") (pinfunction "2_2") (pintype "passive"))
      (node (ref "C19") (pin "1") (pinfunction "1_1") (pintype "passive"))
      (node (ref "IC1") (pin "30") (pinfunction "RESET_30") (pintype "input"))
      (node (ref "ICSP") (pin "5") (pinfunction "5_5") (pintype "bidirectional"))
      (node (ref "RESET-EN") (pin "1") (pinfunction "1_1") (pintype "passive"))
      (node (ref "RESET-EN") (pin "2") (pinfunction "2_2") (pintype "passive"))
      (node (ref "RN2") (pin "1") (pinfunction "1_1") (pintype "passive"))
    )
    (net (code "76") (name "/RESET2") (class "Default")
      (node (ref "IC4") (pin "24") (pinfunction "RESET(PC1/DW)_24") (pintype "input"))
      (node (ref "ICSP1") (pin "5") (pinfunction "5_5") (pintype "bidirectional"))
      (node (ref "RN5") (pin "1") (pinfunction "1_1") (pintype "passive"))
    )
    (net (code "77") (name "/RXD1") (class "Default")
      (node (ref "COMMUNICATION") (pin "6") (pinfunction "6_6") (pintype "passive"))
      (node (ref "IC1") (pin "45") (pinfunction "(RXD1/INT2)PD2_45") (pintype "bidirectional"))
    )
    (net (code "78") (name "/RXD2") (class "Default")
      (node (ref "COMMUNICATION") (pin "4") (pinfunction "4_4") (pintype "passive"))
      (node (ref "IC1") (pin "12") (pinfunction "PH0(RXD2)_12") (pintype "bidirectional"))
    )
    (net (code "79") (name "/RXD3") (class "Default")
      (node (ref "COMMUNICATION") (pin "2") (pinfunction "2_2") (pintype "passive"))
      (node (ref "IC1") (pin "63") (pinfunction "PJ0(RXD3/PCINT9)_63") (pintype "bidirectional"))
    )
    (net (code "80") (name "/RXL") (class "Default")
      (node (ref "IC4") (pin "10") (pinfunction "(INT5/AIN3)PD4_10") (pintype "bidirectional"))
      (node (ref "RX") (pin "C") (pinfunction "C_C") (pintype "passive"))
    )
    (net (code "81") (name "/SCK2") (class "Default")
      (node (ref "IC4") (pin "15") (pinfunction "(SCLK/PCINT1)PB1_15") (pintype "bidirectional"))
      (node (ref "ICSP1") (pin "3") (pinfunction "3_3") (pintype "bidirectional"))
    )
    (net (code "82") (name "/SCL") (class "Default")
      (node (ref "COMMUNICATION") (pin "8") (pinfunction "8_8") (pintype "passive"))
      (node (ref "IC1") (pin "43") (pinfunction "(SCL/INT0)PD0_43") (pintype "bidirectional"))
      (node (ref "RN2") (pin "2") (pinfunction "1_2") (pintype "passive"))
    )
    (net (code "83") (name "/SDA") (class "Default")
      (node (ref "COMMUNICATION") (pin "7") (pinfunction "7_7") (pintype "passive"))
      (node (ref "IC1") (pin "44") (pinfunction "(SDA/INT1)PD1_44") (pintype "bidirectional"))
      (node (ref "RN2") (pin "3") (pinfunction "1_3") (pintype "passive"))
    )
    (net (code "84") (name "/TXD1") (class "Default")
      (node (ref "COMMUNICATION") (pin "5") (pinfunction "5_5") (pintype "passive"))
      (node (ref "IC1") (pin "46") (pinfunction "(TXD1/INT3)PD3_46") (pintype "bidirectional"))
    )
    (net (code "85") (name "/TXD2") (class "Default")
      (node (ref "COMMUNICATION") (pin "3") (pinfunction "3_3") (pintype "passive"))
      (node (ref "IC1") (pin "13") (pinfunction "PH1(TXD2)_13") (pintype "bidirectional"))
    )
    (net (code "86") (name "/TXD3") (class "Default")
      (node (ref "COMMUNICATION") (pin "1") (pinfunction "1_1") (pintype "passive"))
      (node (ref "IC1") (pin "64") (pinfunction "PJ1(TXD3/PCINT10)_64") (pintype "bidirectional"))
    )
    (net (code "87") (name "/TXL") (class "Default")
      (node (ref "IC4") (pin "11") (pinfunction "(XCK/AIN4/PCINT12)PD5_11") (pintype "bidirectional"))
      (node (ref "TX") (pin "C") (pinfunction "C_C") (pintype "passive"))
    )
    (net (code "88") (name "/USBVCC") (class "Default")
      (node (ref "C16") (pin "1") (pinfunction "1_1") (pintype "passive"))
      (node (ref "IC4") (pin "31") (pinfunction "UVCC_31") (pintype "power_in"))
      (node (ref "L1") (pin "2") (pinfunction "2_2") (pintype "passive"))
      (node (ref "T2") (pin "1") (pinfunction "D_1") (pintype "passive"))
    )
    (net (code "89") (name "/VUCAP") (class "Default")
      (node (ref "C18") (pin "2") (pinfunction "2_2") (pintype "passive"))
      (node (ref "IC4") (pin "27") (pinfunction "UCAP_27") (pintype "passive"))
    )
    (net (code "90") (name "/XT1") (class "Default")
      (node (ref "C8") (pin "2") (pinfunction "2_2") (pintype "passive"))
      (node (ref "Q1") (pin "2") (pinfunction "2_2") (pintype "passive"))
    )
    (net (code "91") (name "/XT1R") (class "Default")
      (node (ref "IC4") (pin "1") (pinfunction "XTAL1_1") (pintype "bidirectional"))
      (node (ref "R6") (pin "1") (pinfunction "1_1") (pintype "passive"))
    )
    (net (code "92") (name "/XT2") (class "Default")
      (node (ref "C11") (pin "2") (pinfunction "2_2") (pintype "passive"))
      (node (ref "IC4") (pin "2") (pinfunction "XTAL2(PC0)_2") (pintype "bidirectional"))
      (node (ref "Q1") (pin "1") (pinfunction "1_1") (pintype "passive"))
      (node (ref "R5") (pin "2") (pinfunction "2_2") (pintype "passive"))
      (node (ref "U$22") (pin "1") (pinfunction "1_1") (pintype "passive"))
    )
    (net (code "93") (name "/XTAL1") (class "Default")
      (node (ref "C9") (pin "1") (pinfunction "1_1") (pintype "passive"))
      (node (ref "Q2") (pin "2") (pinfunction "2_2") (pintype "passive"))
    )
    (net (code "94") (name "/XTAL1R") (class "Default")
      (node (ref "IC1") (pin "34") (pinfunction "XTAL1_34") (pintype "input"))
      (node (ref "R1") (pin "2") (pinfunction "2_2") (pintype "passive"))
    )
    (net (code "95") (name "/XTAL2") (class "Default")
      (node (ref "C10") (pin "1") (pinfunction "1_1") (pintype "passive"))
      (node (ref "IC1") (pin "33") (pinfunction "XTAL2_33") (pintype "output"))
      (node (ref "Q2") (pin "1") (pinfunction "1_1") (pintype "passive"))
      (node (ref "R2") (pin "2") (pinfunction "2_2") (pintype "passive"))
      (node (ref "U$9") (pin "1") (pinfunction "1_1") (pintype "passive"))
    )
    (net (code "96") (name "/XVCC") (class "Default")
      (node (ref "CN2") (pin "VBUS") (pinfunction "VBUS_VBUS") (pintype "power_in"))
      (node (ref "L1") (pin "1") (pinfunction "1_1") (pintype "passive"))
    )
    (net (code "97") (name "GND") (class "Default")
      (node (ref "C1") (pin "1") (pinfunction "1_1") (pintype "passive"))
      (node (ref "C10") (pin "2") (pinfunction "2_2") (pintype "passive"))
      (node (ref "C11") (pin "1") (pinfunction "1_1") (pintype "passive"))
      (node (ref "C12") (pin "1") (pinfunction "1_1") (pintype "passive"))
      (node (ref "C13") (pin "1") (pinfunction "1_1") (pintype "passive"))
      (node (ref "C14") (pin "1") (pinfunction "1_1") (pintype "passive"))
      (node (ref "C15") (pin "1") (pinfunction "1_1") (pintype "passive"))
      (node (ref "C16") (pin "2") (pinfunction "2_2") (pintype "passive"))
      (node (ref "C17") (pin "1") (pinfunction "1_1") (pintype "passive"))
      (node (ref "C18") (pin "1") (pinfunction "1_1") (pintype "passive"))
      (node (ref "C2") (pin "1") (pinfunction "1_1") (pintype "passive"))
      (node (ref "C3") (pin "1") (pinfunction "1_1") (pintype "passive"))
      (node (ref "C4") (pin "1") (pinfunction "1_1") (pintype "passive"))
      (node (ref "C5") (pin "-") (pinfunction "-_-") (pintype "passive"))
      (node (ref "C6") (pin "1") (pinfunction "1_1") (pintype "passive"))
      (node (ref "C7") (pin "-") (pinfunction "-_-") (pintype "passive"))
      (node (ref "C8") (pin "1") (pinfunction "1_1") (pintype "passive"))
      (node (ref "C9") (pin "2") (pinfunction "2_2") (pintype "passive"))
      (node (ref "CN1") (pin "GND") (pinfunction "GND_GND") (pintype "power_in"))
      (node (ref "CN1") (pin "GNDBREAK") (pinfunction "GNDBREAK_GNDBREAK") (pintype "power_in"))
      (node (ref "CN2") (pin "GND") (pinfunction "GND_GND") (pintype "power_in"))
      (node (ref "CN2") (pin "ID") (pinfunction "ID_ID") (pintype "bidirectional"))
      (node (ref "IC1") (pin "11") (pinfunction "GND_11") (pintype "power_in"))
      (node (ref "IC1") (pin "32") (pinfunction "GND1_32") (pintype "power_in"))
      (node (ref "IC1") (pin "62") (pinfunction "GND2_62") (pintype "power_in"))
      (node (ref "IC1") (pin "81") (pinfunction "GND3_81") (pintype "power_in"))
      (node (ref "IC1") (pin "99") (pinfunction "AGND_99") (pintype "power_in"))
      (node (ref "IC2") (pin "1") (pinfunction "GND/ADJ_1") (pintype "input"))
      (node (ref "IC3") (pin "1") (pinfunction "ADJ_1") (pintype "input"))
      (node (ref "IC4") (pin "28") (pinfunction "UGND_28") (pintype "power_in"))
      (node (ref "IC4") (pin "3") (pinfunction "GND_3") (pintype "power_in"))
      (node (ref "IC4") (pin "EXP") (pinfunction "PAD_EXP") (pintype "power_in"))
      (node (ref "IC5") (pin "2") (pinfunction "-IN_2") (pintype "input"))
      (node (ref "IC5") (pin "3") (pinfunction "+IN_3") (pintype "input"))
      (node (ref "IC5") (pin "4") (pinfunction "V-_4") (pintype "power_in"))
      (node (ref "IC6") (pin "2") (pinfunction "GND_2") (pintype "power_in"))
      (node (ref "ICSP") (pin "6") (pinfunction "6_6") (pintype "bidirectional"))
      (node (ref "ICSP1") (pin "6") (pinfunction "6_6") (pintype "bidirectional"))
      (node (ref "JP3") (pin "1") (pinfunction "1_1") (pintype "passive"))
      (node (ref "JP4") (pin "1") (pinfunction "1_1") (pintype "passive"))
      (node (ref "L2") (pin "2") (pinfunction "2_2") (pintype "passive"))
      (node (ref "LED1") (pin "C") (pinfunction "C_C") (pintype "passive"))
      (node (ref "LED2") (pin "C") (pinfunction "C_C") (pintype "passive"))
      (node (ref "POWER") (pin "4") (pinfunction "4_4") (pintype "passive"))
      (node (ref "POWER") (pin "5") (pinfunction "5_5") (pintype "passive"))
      (node (ref "PWMH") (pin "7") (pinfunction "7_7") (pintype "passive"))
      (node (ref "RN5") (pin "2") (pinfunction "1_2") (pintype "passive"))
      (node (ref "S1") (pin "1") (pinfunction "1_1") (pintype "passive"))
      (node (ref "S1") (pin "2") (pinfunction "2_2") (pintype "passive"))
      (node (ref "U$22") (pin "2") (pinfunction "2_2") (pintype "passive"))
      (node (ref "U$9") (pin "2") (pinfunction "2_2") (pintype "passive"))
      (node (ref "UBOOT") (pin "2") (pinfunction "2_2") (pintype "passive"))
    )
    (net (code "98") (name "Net-(CN1-PadPWR)") (class "Default")
      (node (ref "CN1") (pin "PWR") (pinfunction "PWR_PWR") (pintype "power_in"))
      (node (ref "D1") (pin "A") (pinfunction "A_A") (pintype "passive"))
    )
    (net (code "99") (name "Net-(CN2-PadD+)") (class "Default")
      (node (ref "CN2") (pin "D+") (pinfunction "D+_D+") (pintype "bidirectional"))
      (node (ref "R3") (pin "1") (pinfunction "1_1") (pintype "passive"))
      (node (ref "RN3") (pin "1") (pinfunction "1_1") (pintype "passive"))
    )
    (net (code "100") (name "Net-(L2-Pad1)") (class "Default")
      (node (ref "L2") (pin "1") (pinfunction "1_1") (pintype "passive"))
      (node (ref "R3") (pin "2") (pinfunction "2_2") (pintype "passive"))
      (node (ref "R4") (pin "2") (pinfunction "2_2") (pintype "passive"))
    )
    (net (code "101") (name "Net-(POWER-Pad1)") (class "Default")
      (node (ref "POWER") (pin "1") (pinfunction "1_1") (pintype "passive"))
      (node (ref "S1") (pin "3") (pinfunction "3_3") (pintype "passive"))
      (node (ref "S1") (pin "4") (pinfunction "4_4") (pintype "passive"))
    )
    (net (code "102") (name "Net-(R1-Pad1)") (class "Default")
      (node (ref "R1") (pin "1") (pinfunction "1_1") (pintype "passive"))
      (node (ref "R2") (pin "1") (pinfunction "1_1") (pintype "passive"))
      (node (ref "U$9") (pin "3") (pinfunction "3_3") (pintype "passive"))
    )
    (net (code "103") (name "Net-(R5-Pad1)") (class "Default")
      (node (ref "R5") (pin "1") (pinfunction "1_1") (pintype "passive"))
      (node (ref "R6") (pin "2") (pinfunction "2_2") (pintype "passive"))
      (node (ref "U$22") (pin "3") (pinfunction "3_3") (pintype "passive"))
    )
    (net (code "104") (name "Net-(RN1C-2)") (class "Default")
      (node (ref "LED2") (pin "A") (pinfunction "A_A") (pintype "passive"))
      (node (ref "RN1") (pin "6") (pinfunction "2_6") (pintype "passive"))
    )
    (net (code "105") (name "Net-(RN1D-2)") (class "Default")
      (node (ref "LED1") (pin "A") (pinfunction "A_A") (pintype "passive"))
      (node (ref "RN1") (pin "5") (pinfunction "2_5") (pintype "passive"))
    )
    (net (code "106") (name "Net-(RN3D-1)") (class "Default")
      (node (ref "CN2") (pin "D-") (pinfunction "D-_D-") (pintype "bidirectional"))
      (node (ref "R4") (pin "1") (pinfunction "1_1") (pintype "passive"))
      (node (ref "RN3") (pin "4") (pinfunction "1_4") (pintype "passive"))
    )
    (net (code "107") (name "Net-(RN4C-1)") (class "Default")
      (node (ref "RN4") (pin "3") (pinfunction "1_3") (pintype "passive"))
      (node (ref "TX") (pin "A") (pinfunction "A_A") (pintype "passive"))
    )
    (net (code "108") (name "Net-(RN4D-1)") (class "Default")
      (node (ref "RN4") (pin "4") (pinfunction "1_4") (pintype "passive"))
      (node (ref "RX") (pin "A") (pinfunction "A_A") (pintype "passive"))
    )
    (net (code "109") (name "VIN") (class "Default")
      (node (ref "C5") (pin "+") (pinfunction "+_+") (pintype "passive"))
      (node (ref "C6") (pin "2") (pinfunction "2_2") (pintype "passive"))
      (node (ref "D1") (pin "C") (pinfunction "C_C") (pintype "passive"))
      (node (ref "IC2") (pin "3") (pinfunction "IN_3") (pintype "input"))
      (node (ref "IC3") (pin "3") (pinfunction "VI_3") (pintype "input"))
      (node (ref "POWER") (pin "6") (pinfunction "6_6") (pintype "passive"))
      (node (ref "RN5") (pin "6") (pinfunction "2_6") (pintype "passive"))
    )
    (net (code "110") (name "unconnected-(IC1-(CLKO{slash}ICP3{slash}INT7)PE7-Pad9)") (class "Default")
      (node (ref "IC1") (pin "9") (pinfunction "(CLKO/ICP3/INT7)PE7_9") (pintype "bidirectional"))
    )
    (net (code "111") (name "unconnected-(IC1-(ICP1)PD4-Pad47)") (class "Default")
      (node (ref "IC1") (pin "47") (pinfunction "(ICP1)PD4_47") (pintype "bidirectional"))
    )
    (net (code "112") (name "unconnected-(IC1-(T1)PD6-Pad49)") (class "Default")
      (node (ref "IC1") (pin "49") (pinfunction "(T1)PD6_49") (pintype "bidirectional"))
    )
    (net (code "113") (name "unconnected-(IC1-(T3{slash}INT6)PE6-Pad8)") (class "Default")
      (node (ref "IC1") (pin "8") (pinfunction "(T3/INT6)PE6_8") (pintype "bidirectional"))
    )
    (net (code "114") (name "unconnected-(IC1-(TOSC1)PG4-Pad29)") (class "Default")
      (node (ref "IC1") (pin "29") (pinfunction "(TOSC1)PG4_29") (pintype "bidirectional"))
    )
    (net (code "115") (name "unconnected-(IC1-(TOSC2)PG3-Pad28)") (class "Default")
      (node (ref "IC1") (pin "28") (pinfunction "(TOSC2)PG3_28") (pintype "bidirectional"))
    )
    (net (code "116") (name "unconnected-(IC1-(XCK0{slash}AIN0)PE2-Pad4)") (class "Default")
      (node (ref "IC1") (pin "4") (pinfunction "(XCK0/AIN0)PE2_4") (pintype "bidirectional"))
    )
    (net (code "117") (name "unconnected-(IC1-(XCK1)PD5-Pad48)") (class "Default")
      (node (ref "IC1") (pin "48") (pinfunction "(XCK1)PD5_48") (pintype "bidirectional"))
    )
    (net (code "118") (name "unconnected-(IC1-PH2(XCK2)-Pad14)") (class "Default")
      (node (ref "IC1") (pin "14") (pinfunction "PH2(XCK2)_14") (pintype "bidirectional"))
    )
    (net (code "119") (name "unconnected-(IC1-PH7(T4)-Pad27)") (class "Default")
      (node (ref "IC1") (pin "27") (pinfunction "PH7(T4)_27") (pintype "bidirectional"))
    )
    (net (code "120") (name "unconnected-(IC1-PJ2(XCK3{slash}PCINT11)-Pad65)") (class "Default")
      (node (ref "IC1") (pin "65") (pinfunction "PJ2(XCK3/PCINT11)_65") (pintype "bidirectional"))
    )
    (net (code "121") (name "unconnected-(IC1-PJ3(PCINT12)-Pad66)") (class "Default")
      (node (ref "IC1") (pin "66") (pinfunction "PJ3(PCINT12)_66") (pintype "bidirectional"))
    )
    (net (code "122") (name "unconnected-(IC1-PJ4(PCINT13)-Pad67)") (class "Default")
      (node (ref "IC1") (pin "67") (pinfunction "PJ4(PCINT13)_67") (pintype "bidirectional"))
    )
    (net (code "123") (name "unconnected-(IC1-PJ5(PCINT14)-Pad68)") (class "Default")
      (node (ref "IC1") (pin "68") (pinfunction "PJ5(PCINT14)_68") (pintype "bidirectional"))
    )
    (net (code "124") (name "unconnected-(IC1-PJ6(PCINT15)-Pad69)") (class "Default")
      (node (ref "IC1") (pin "69") (pinfunction "PJ6(PCINT15)_69") (pintype "bidirectional"))
    )
    (net (code "125") (name "unconnected-(IC1-PJ7-Pad79)") (class "Default")
      (node (ref "IC1") (pin "79") (pinfunction "PJ7_79") (pintype "bidirectional"))
    )
    (net (code "126") (name "unconnected-(IC4-(AIN0{slash}INT1)PD1-Pad7)") (class "Default")
      (node (ref "IC4") (pin "7") (pinfunction "(AIN0/INT1)PD1_7") (pintype "bidirectional"))
    )
    (net (code "127") (name "unconnected-(IC4-(AIN2{slash}PCINT11)PC2-Pad5)") (class "Default")
      (node (ref "IC4") (pin "5") (pinfunction "(AIN2/PCINT11)PC2_5") (pintype "bidirectional"))
    )
    (net (code "128") (name "unconnected-(IC4-(INT4{slash}ICP1{slash}CLK0)PC7-Pad22)") (class "Default")
      (node (ref "IC4") (pin "22") (pinfunction "(INT4/ICP1/CLK0)PC7_22") (pintype "bidirectional"))
    )
    (net (code "129") (name "unconnected-(IC4-(OC0B{slash}INT0)PD0-Pad6)") (class "Default")
      (node (ref "IC4") (pin "6") (pinfunction "(OC0B/INT0)PD0_6") (pintype "bidirectional"))
    )
    (net (code "130") (name "unconnected-(IC4-(OC1A{slash}PCINT8)PC6-Pad23)") (class "Default")
      (node (ref "IC4") (pin "23") (pinfunction "(OC1A/PCINT8)PC6_23") (pintype "bidirectional"))
    )
    (net (code "131") (name "unconnected-(IC4-(PCINT5)PB5-Pad19)") (class "Default")
      (node (ref "IC4") (pin "19") (pinfunction "(PCINT5)PB5_19") (pintype "bidirectional"))
    )
    (net (code "132") (name "unconnected-(IC4-(PCINT6)PB6-Pad20)") (class "Default")
      (node (ref "IC4") (pin "20") (pinfunction "(PCINT6)PB6_20") (pintype "bidirectional"))
    )
    (net (code "133") (name "unconnected-(IC4-(PCINT7{slash}OC0A{slash}OC1C)PB7-Pad21)") (class "Default")
      (node (ref "IC4") (pin "21") (pinfunction "(PCINT7/OC0A/OC1C)PB7_21") (pintype "bidirectional"))
    )
    (net (code "134") (name "unconnected-(IC4-(PCINT9{slash}OC1B)PC5-Pad25)") (class "Default")
      (node (ref "IC4") (pin "25") (pinfunction "(PCINT9/OC1B)PC5_25") (pintype "bidirectional"))
    )
    (net (code "135") (name "unconnected-(IC4-(PCINT10)PC4-Pad26)") (class "Default")
      (node (ref "IC4") (pin "26") (pinfunction "(PCINT10)PC4_26") (pintype "bidirectional"))
    )
    (net (code "136") (name "unconnected-(IC4-(RTS{slash}AIN5{slash}INT6)PD6-Pad12)") (class "Default")
      (node (ref "IC4") (pin "12") (pinfunction "(RTS/AIN5/INT6)PD6_12") (pintype "bidirectional"))
    )
    (net (code "137") (name "unconnected-(IC4-(SS{slash}PCINT0)PB0-Pad14)") (class "Default")
      (node (ref "IC4") (pin "14") (pinfunction "(SS/PCINT0)PB0_14") (pintype "bidirectional"))
    )
    (net (code "138") (name "unconnected-(IC4-(T1{slash}PCINT4)PB4-Pad18)") (class "Default")
      (node (ref "IC4") (pin "18") (pinfunction "(T1/PCINT4)PB4_18") (pintype "bidirectional"))
    )
    (net (code "139") (name "unconnected-(IC5A-OUT-Pad1)") (class "Default")
      (node (ref "IC5") (pin "1") (pinfunction "OUT_1") (pintype "output"))
    )
    (net (code "140") (name "unconnected-(IC6-NC{slash}FB-Pad4)") (class "Default")
      (node (ref "IC6") (pin "4") (pinfunction "NC/FB_4") (pintype "passive"))
    )
    (net (code "141") (name "unconnected-(RN1-Pad1)") (class "Default")
      (node (ref "RN1") (pin "1") (pinfunction "1_1") (pintype "passive"))
    )
    (net (code "142") (name "unconnected-(RN1A-2-Pad8)") (class "Default")
      (node (ref "RN1") (pin "8") (pinfunction "2_8") (pintype "passive"))
    )
    (net (code "143") (name "unconnected-(RN1B-1-Pad2)") (class "Default")
      (node (ref "RN1") (pin "2") (pinfunction "1_2") (pintype "passive"))
    )
    (net (code "144") (name "unconnected-(RN1B-2-Pad7)") (class "Default")
      (node (ref "RN1") (pin "7") (pinfunction "2_7") (pintype "passive"))
    )
    (net (code "145") (name "unconnected-(RN2D-1-Pad4)") (class "Default")
      (node (ref "RN2") (pin "4") (pinfunction "1_4") (pintype "passive"))
    )
    (net (code "146") (name "unconnected-(RN2D-2-Pad5)") (class "Default")
      (node (ref "RN2") (pin "5") (pinfunction "2_5") (pintype "passive"))
    )
    (net (code "147") (name "unconnected-(RN3B-1-Pad2)") (class "Default")
      (node (ref "RN3") (pin "2") (pinfunction "1_2") (pintype "passive"))
    )
    (net (code "148") (name "unconnected-(RN3B-2-Pad7)") (class "Default")
      (node (ref "RN3") (pin "7") (pinfunction "2_7") (pintype "passive"))
    )
    (net (code "149") (name "unconnected-(RN3C-1-Pad3)") (class "Default")
      (node (ref "RN3") (pin "3") (pinfunction "1_3") (pintype "passive"))
    )
    (net (code "150") (name "unconnected-(RN3C-2-Pad6)") (class "Default")
      (node (ref "RN3") (pin "6") (pinfunction "2_6") (pintype "passive"))
    )
    (net (code "151") (name "unconnected-(RN5D-1-Pad4)") (class "Default")
      (node (ref "RN5") (pin "4") (pinfunction "1_4") (pintype "passive"))
    )
    (net (code "152") (name "unconnected-(RN5D-2-Pad5)") (class "Default")
      (node (ref "RN5") (pin "5") (pinfunction "2_5") (pintype "passive"))
    )
  )
)
